# top.net
KiCad netlist of a schematic drawn in Altium Designer
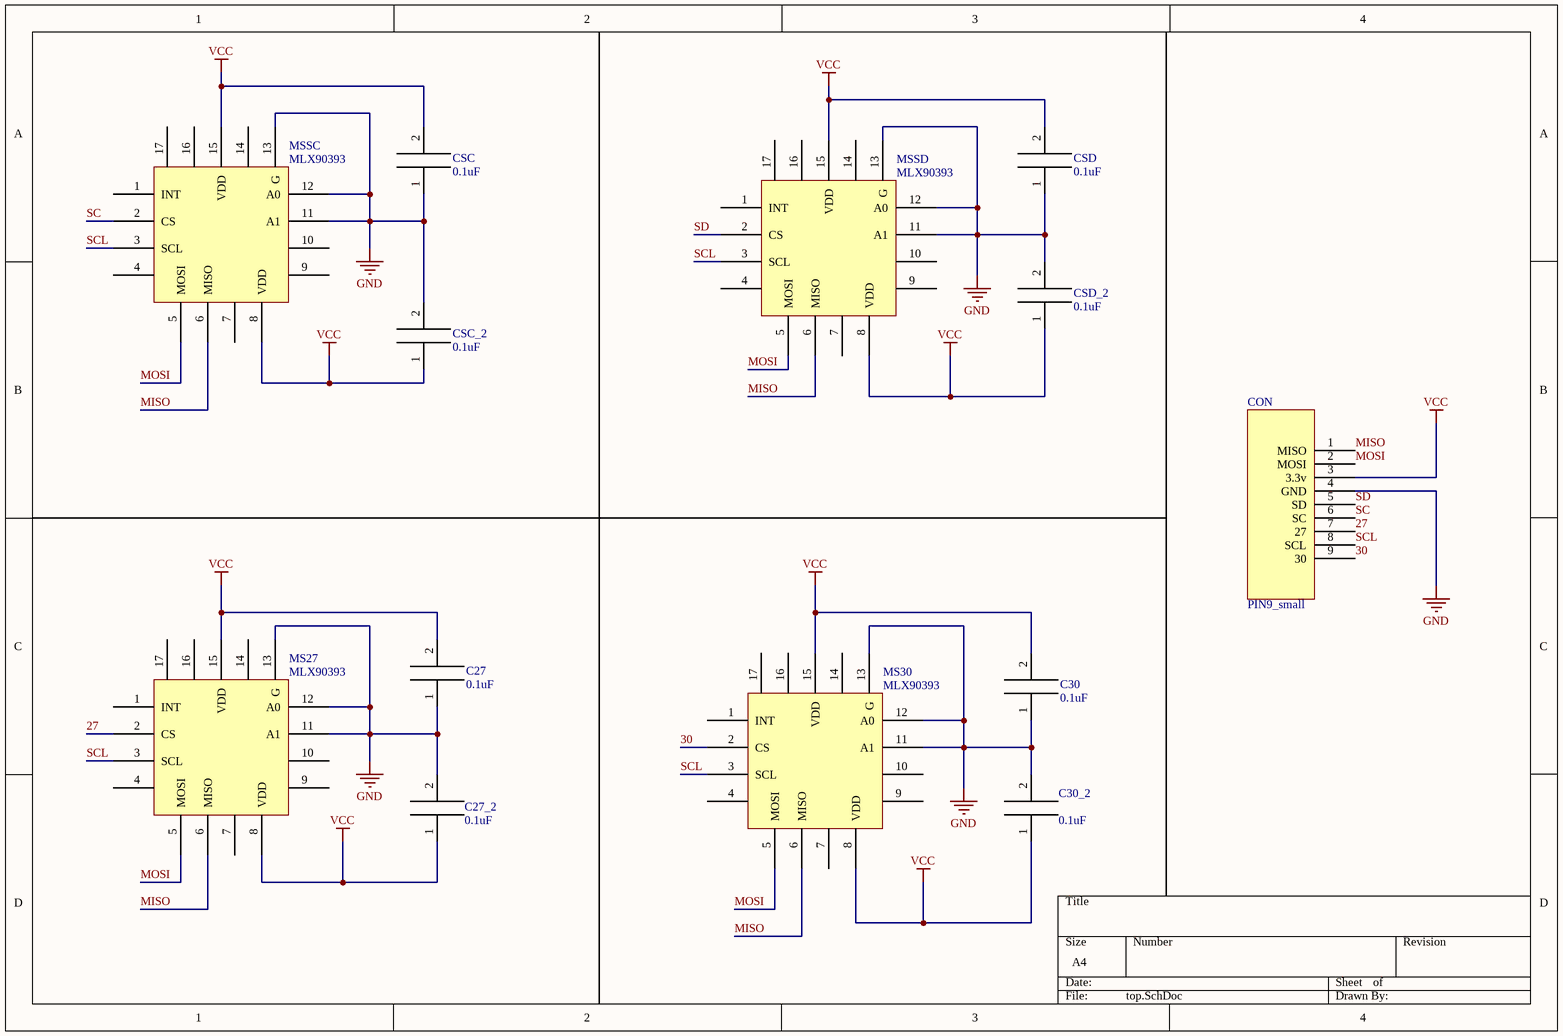
[diagram p0: top.SchDoc]

(export (version "E")
  (design (tool "Eeschema 10.0.6"))
  (components
    (comp (ref "C27")
      (value "0.1uF")
      (footprint "CAP_0603")
      (description "capacitance")
      (libsource (lib "MAGNETO") (part "CAP"))
    )
    (comp (ref "C27_2")
      (value "0.1uF")
      (footprint "CAP_0603")
      (description "capacitance")
      (libsource (lib "MAGNETO") (part "CAP"))
    )
    (comp (ref "C30")
      (value "0.1uF")
      (footprint "CAP_0603")
      (description "capacitance")
      (libsource (lib "MAGNETO") (part "CAP"))
    )
    (comp (ref "C30_2")
      (value "0.1uF")
      (footprint "CAP_0603")
      (description "capacitance")
      (libsource (lib "MAGNETO") (part "CAP"))
    )
    (comp (ref "CON")
      (value "PIN9_small")
      (footprint "PIN9_small")
      (libsource (lib "MAGNETO") (part "PIN9_small"))
    )
    (comp (ref "CSC")
      (value "0.1uF")
      (footprint "CAP_0603")
      (description "capacitance")
      (libsource (lib "MAGNETO") (part "CAP"))
    )
    (comp (ref "CSC_2")
      (value "0.1uF")
      (footprint "CAP_0603")
      (description "capacitance")
      (libsource (lib "MAGNETO") (part "CAP"))
    )
    (comp (ref "CSD")
      (value "0.1uF")
      (footprint "CAP_0603")
      (description "capacitance")
      (libsource (lib "MAGNETO") (part "CAP"))
    )
    (comp (ref "CSD_2")
      (value "0.1uF")
      (footprint "CAP_0603")
      (description "capacitance")
      (libsource (lib "MAGNETO") (part "CAP"))
    )
    (comp (ref "MS27")
      (value "MLX90393")
      (footprint "MLX90393")
      (description "sensor")
      (libsource (lib "MAGNETO") (part "MLX90393"))
    )
    (comp (ref "MS30")
      (value "MLX90393")
      (footprint "MLX90393")
      (description "sensor")
      (libsource (lib "MAGNETO") (part "MLX90393"))
    )
    (comp (ref "MSSC")
      (value "MLX90393")
      (footprint "MLX90393")
      (description "sensor")
      (libsource (lib "MAGNETO") (part "MLX90393"))
    )
    (comp (ref "MSSD")
      (value "MLX90393")
      (footprint "MLX90393")
      (description "sensor")
      (libsource (lib "MAGNETO") (part "MLX90393"))
    )
  )
  (nets
    (net (code "1") (name "/27") (class "Default")
      (node (ref "CON") (pin "7") (pinfunction "27_7") (pintype "passive"))
      (node (ref "MS27") (pin "2") (pinfunction "CS_2") (pintype "passive"))
    )
    (net (code "2") (name "/30") (class "Default")
      (node (ref "CON") (pin "9") (pinfunction "30_9") (pintype "passive"))
      (node (ref "MS30") (pin "2") (pinfunction "CS_2") (pintype "passive"))
    )
    (net (code "3") (name "/MISO") (class "Default")
      (node (ref "CON") (pin "1") (pinfunction "MISO_1") (pintype "passive"))
      (node (ref "MS27") (pin "6") (pinfunction "MISO_6") (pintype "passive"))
      (node (ref "MS30") (pin "6") (pinfunction "MISO_6") (pintype "passive"))
      (node (ref "MSSC") (pin "6") (pinfunction "MISO_6") (pintype "passive"))
      (node (ref "MSSD") (pin "6") (pinfunction "MISO_6") (pintype "passive"))
    )
    (net (code "4") (name "/MOSI") (class "Default")
      (node (ref "CON") (pin "2") (pinfunction "MOSI_2") (pintype "passive"))
      (node (ref "MS27") (pin "5") (pinfunction "MOSI_5") (pintype "passive"))
      (node (ref "MS30") (pin "5") (pinfunction "MOSI_5") (pintype "passive"))
      (node (ref "MSSC") (pin "5") (pinfunction "MOSI_5") (pintype "passive"))
      (node (ref "MSSD") (pin "5") (pinfunction "MOSI_5") (pintype "passive"))
    )
    (net (code "5") (name "/SC") (class "Default")
      (node (ref "CON") (pin "6") (pinfunction "SC_6") (pintype "passive"))
      (node (ref "MSSC") (pin "2") (pinfunction "CS_2") (pintype "passive"))
    )
    (net (code "6") (name "/SCL") (class "Default")
      (node (ref "CON") (pin "8") (pinfunction "SCL_8") (pintype "passive"))
      (node (ref "MS27") (pin "3") (pinfunction "SCL_3") (pintype "passive"))
      (node (ref "MS30") (pin "3") (pinfunction "SCL_3") (pintype "passive"))
      (node (ref "MSSC") (pin "3") (pinfunction "SCL_3") (pintype "passive"))
      (node (ref "MSSD") (pin "3") (pinfunction "SCL_3") (pintype "passive"))
    )
    (net (code "7") (name "/SD") (class "Default")
      (node (ref "CON") (pin "5") (pinfunction "SD_5") (pintype "passive"))
      (node (ref "MSSD") (pin "2") (pinfunction "CS_2") (pintype "passive"))
    )
    (net (code "8") (name "GND") (class "Default")
      (node (ref "C27") (pin "1") (pintype "passive"))
      (node (ref "C27_2") (pin "2") (pintype "passive"))
      (node (ref "C30") (pin "1") (pintype "passive"))
      (node (ref "C30_2") (pin "2") (pintype "passive"))
      (node (ref "CON") (pin "4") (pinfunction "GND_4") (pintype "passive"))
      (node (ref "CSC") (pin "1") (pintype "passive"))
      (node (ref "CSC_2") (pin "2") (pintype "passive"))
      (node (ref "CSD") (pin "1") (pintype "passive"))
      (node (ref "CSD_2") (pin "2") (pintype "passive"))
      (node (ref "MS27") (pin "11") (pinfunction "A1_11") (pintype "passive"))
      (node (ref "MS27") (pin "12") (pinfunction "A0_12") (pintype "passive"))
      (node (ref "MS27") (pin "13") (pinfunction "G_13") (pintype "passive"))
      (node (ref "MS30") (pin "11") (pinfunction "A1_11") (pintype "passive"))
      (node (ref "MS30") (pin "12") (pinfunction "A0_12") (pintype "passive"))
      (node (ref "MS30") (pin "13") (pinfunction "G_13") (pintype "passive"))
      (node (ref "MSSC") (pin "11") (pinfunction "A1_11") (pintype "passive"))
      (node (ref "MSSC") (pin "12") (pinfunction "A0_12") (pintype "passive"))
      (node (ref "MSSC") (pin "13") (pinfunction "G_13") (pintype "passive"))
      (node (ref "MSSD") (pin "11") (pinfunction "A1_11") (pintype "passive"))
      (node (ref "MSSD") (pin "12") (pinfunction "A0_12") (pintype "passive"))
      (node (ref "MSSD") (pin "13") (pinfunction "G_13") (pintype "passive"))
    )
    (net (code "9") (name "VCC") (class "Default")
      (node (ref "C27") (pin "2") (pintype "passive"))
      (node (ref "C27_2") (pin "1") (pintype "passive"))
      (node (ref "C30") (pin "2") (pintype "passive"))
      (node (ref "C30_2") (pin "1") (pintype "passive"))
      (node (ref "CON") (pin "3") (pinfunction "3.3v_3") (pintype "passive"))
      (node (ref "CSC") (pin "2") (pintype "passive"))
      (node (ref "CSC_2") (pin "1") (pintype "passive"))
      (node (ref "CSD") (pin "2") (pintype "passive"))
      (node (ref "CSD_2") (pin "1") (pintype "passive"))
      (node (ref "MS27") (pin "15") (pinfunction "VDD_15") (pintype "passive"))
      (node (ref "MS27") (pin "8") (pinfunction "VDD_8") (pintype "passive"))
      (node (ref "MS30") (pin "15") (pinfunction "VDD_15") (pintype "passive"))
      (node (ref "MS30") (pin "8") (pinfunction "VDD_8") (pintype "passive"))
      (node (ref "MSSC") (pin "15") (pinfunction "VDD_15") (pintype "passive"))
      (node (ref "MSSC") (pin "8") (pinfunction "VDD_8") (pintype "passive"))
      (node (ref "MSSD") (pin "15") (pinfunction "VDD_15") (pintype "passive"))
      (node (ref "MSSD") (pin "8") (pinfunction "VDD_8") (pintype "passive"))
    )
    (net (code "10") (name "unconnected-(MS27-INT-Pad1)") (class "Default")
      (node (ref "MS27") (pin "1") (pinfunction "INT_1") (pintype "passive"))
    )
    (net (code "11") (name "unconnected-(MS27-Pad4)") (class "Default")
      (node (ref "MS27") (pin "4") (pintype "passive"))
    )
    (net (code "12") (name "unconnected-(MS27-Pad7)") (class "Default")
      (node (ref "MS27") (pin "7") (pintype "passive"))
    )
    (net (code "13") (name "unconnected-(MS27-Pad9)") (class "Default")
      (node (ref "MS27") (pin "9") (pintype "passive"))
    )
    (net (code "14") (name "unconnected-(MS27-Pad10)") (class "Default")
      (node (ref "MS27") (pin "10") (pintype "passive"))
    )
    (net (code "15") (name "unconnected-(MS27-Pad14)") (class "Default")
      (node (ref "MS27") (pin "14") (pintype "passive"))
    )
    (net (code "16") (name "unconnected-(MS27-Pad16)") (class "Default")
      (node (ref "MS27") (pin "16") (pintype "passive"))
    )
    (net (code "17") (name "unconnected-(MS27-Pad17)") (class "Default")
      (node (ref "MS27") (pin "17") (pinfunction "17_17") (pintype "passive"))
    )
    (net (code "18") (name "unconnected-(MS30-INT-Pad1)") (class "Default")
      (node (ref "MS30") (pin "1") (pinfunction "INT_1") (pintype "passive"))
    )
    (net (code "19") (name "unconnected-(MS30-Pad4)") (class "Default")
      (node (ref "MS30") (pin "4") (pintype "passive"))
    )
    (net (code "20") (name "unconnected-(MS30-Pad7)") (class "Default")
      (node (ref "MS30") (pin "7") (pintype "passive"))
    )
    (net (code "21") (name "unconnected-(MS30-Pad9)") (class "Default")
      (node (ref "MS30") (pin "9") (pintype "passive"))
    )
    (net (code "22") (name "unconnected-(MS30-Pad10)") (class "Default")
      (node (ref "MS30") (pin "10") (pintype "passive"))
    )
    (net (code "23") (name "unconnected-(MS30-Pad14)") (class "Default")
      (node (ref "MS30") (pin "14") (pintype "passive"))
    )
    (net (code "24") (name "unconnected-(MS30-Pad16)") (class "Default")
      (node (ref "MS30") (pin "16") (pintype "passive"))
    )
    (net (code "25") (name "unconnected-(MS30-Pad17)") (class "Default")
      (node (ref "MS30") (pin "17") (pinfunction "17_17") (pintype "passive"))
    )
    (net (code "26") (name "unconnected-(MSSC-INT-Pad1)") (class "Default")
      (node (ref "MSSC") (pin "1") (pinfunction "INT_1") (pintype "passive"))
    )
    (net (code "27") (name "unconnected-(MSSC-Pad4)") (class "Default")
      (node (ref "MSSC") (pin "4") (pintype "passive"))
    )
    (net (code "28") (name "unconnected-(MSSC-Pad7)") (class "Default")
      (node (ref "MSSC") (pin "7") (pintype "passive"))
    )
    (net (code "29") (name "unconnected-(MSSC-Pad9)") (class "Default")
      (node (ref "MSSC") (pin "9") (pintype "passive"))
    )
    (net (code "30") (name "unconnected-(MSSC-Pad10)") (class "Default")
      (node (ref "MSSC") (pin "10") (pintype "passive"))
    )
    (net (code "31") (name "unconnected-(MSSC-Pad14)") (class "Default")
      (node (ref "MSSC") (pin "14") (pintype "passive"))
    )
    (net (code "32") (name "unconnected-(MSSC-Pad16)") (class "Default")
      (node (ref "MSSC") (pin "16") (pintype "passive"))
    )
    (net (code "33") (name "unconnected-(MSSC-Pad17)") (class "Default")
      (node (ref "MSSC") (pin "17") (pinfunction "17_17") (pintype "passive"))
    )
    (net (code "34") (name "unconnected-(MSSD-INT-Pad1)") (class "Default")
      (node (ref "MSSD") (pin "1") (pinfunction "INT_1") (pintype "passive"))
    )
    (net (code "35") (name "unconnected-(MSSD-Pad4)") (class "Default")
      (node (ref "MSSD") (pin "4") (pintype "passive"))
    )
    (net (code "36") (name "unconnected-(MSSD-Pad7)") (class "Default")
      (node (ref "MSSD") (pin "7") (pintype "passive"))
    )
    (net (code "37") (name "unconnected-(MSSD-Pad9)") (class "Default")
      (node (ref "MSSD") (pin "9") (pintype "passive"))
    )
    (net (code "38") (name "unconnected-(MSSD-Pad10)") (class "Default")
      (node (ref "MSSD") (pin "10") (pintype "passive"))
    )
    (net (code "39") (name "unconnected-(MSSD-Pad14)") (class "Default")
      (node (ref "MSSD") (pin "14") (pintype "passive"))
    )
    (net (code "40") (name "unconnected-(MSSD-Pad16)") (class "Default")
      (node (ref "MSSD") (pin "16") (pintype "passive"))
    )
    (net (code "41") (name "unconnected-(MSSD-Pad17)") (class "Default")
      (node (ref "MSSD") (pin "17") (pinfunction "17_17") (pintype "passive"))
    )
  )
)
